# lightbulb-clock.net
KiCad netlist of a schematic drawn in EAGLE
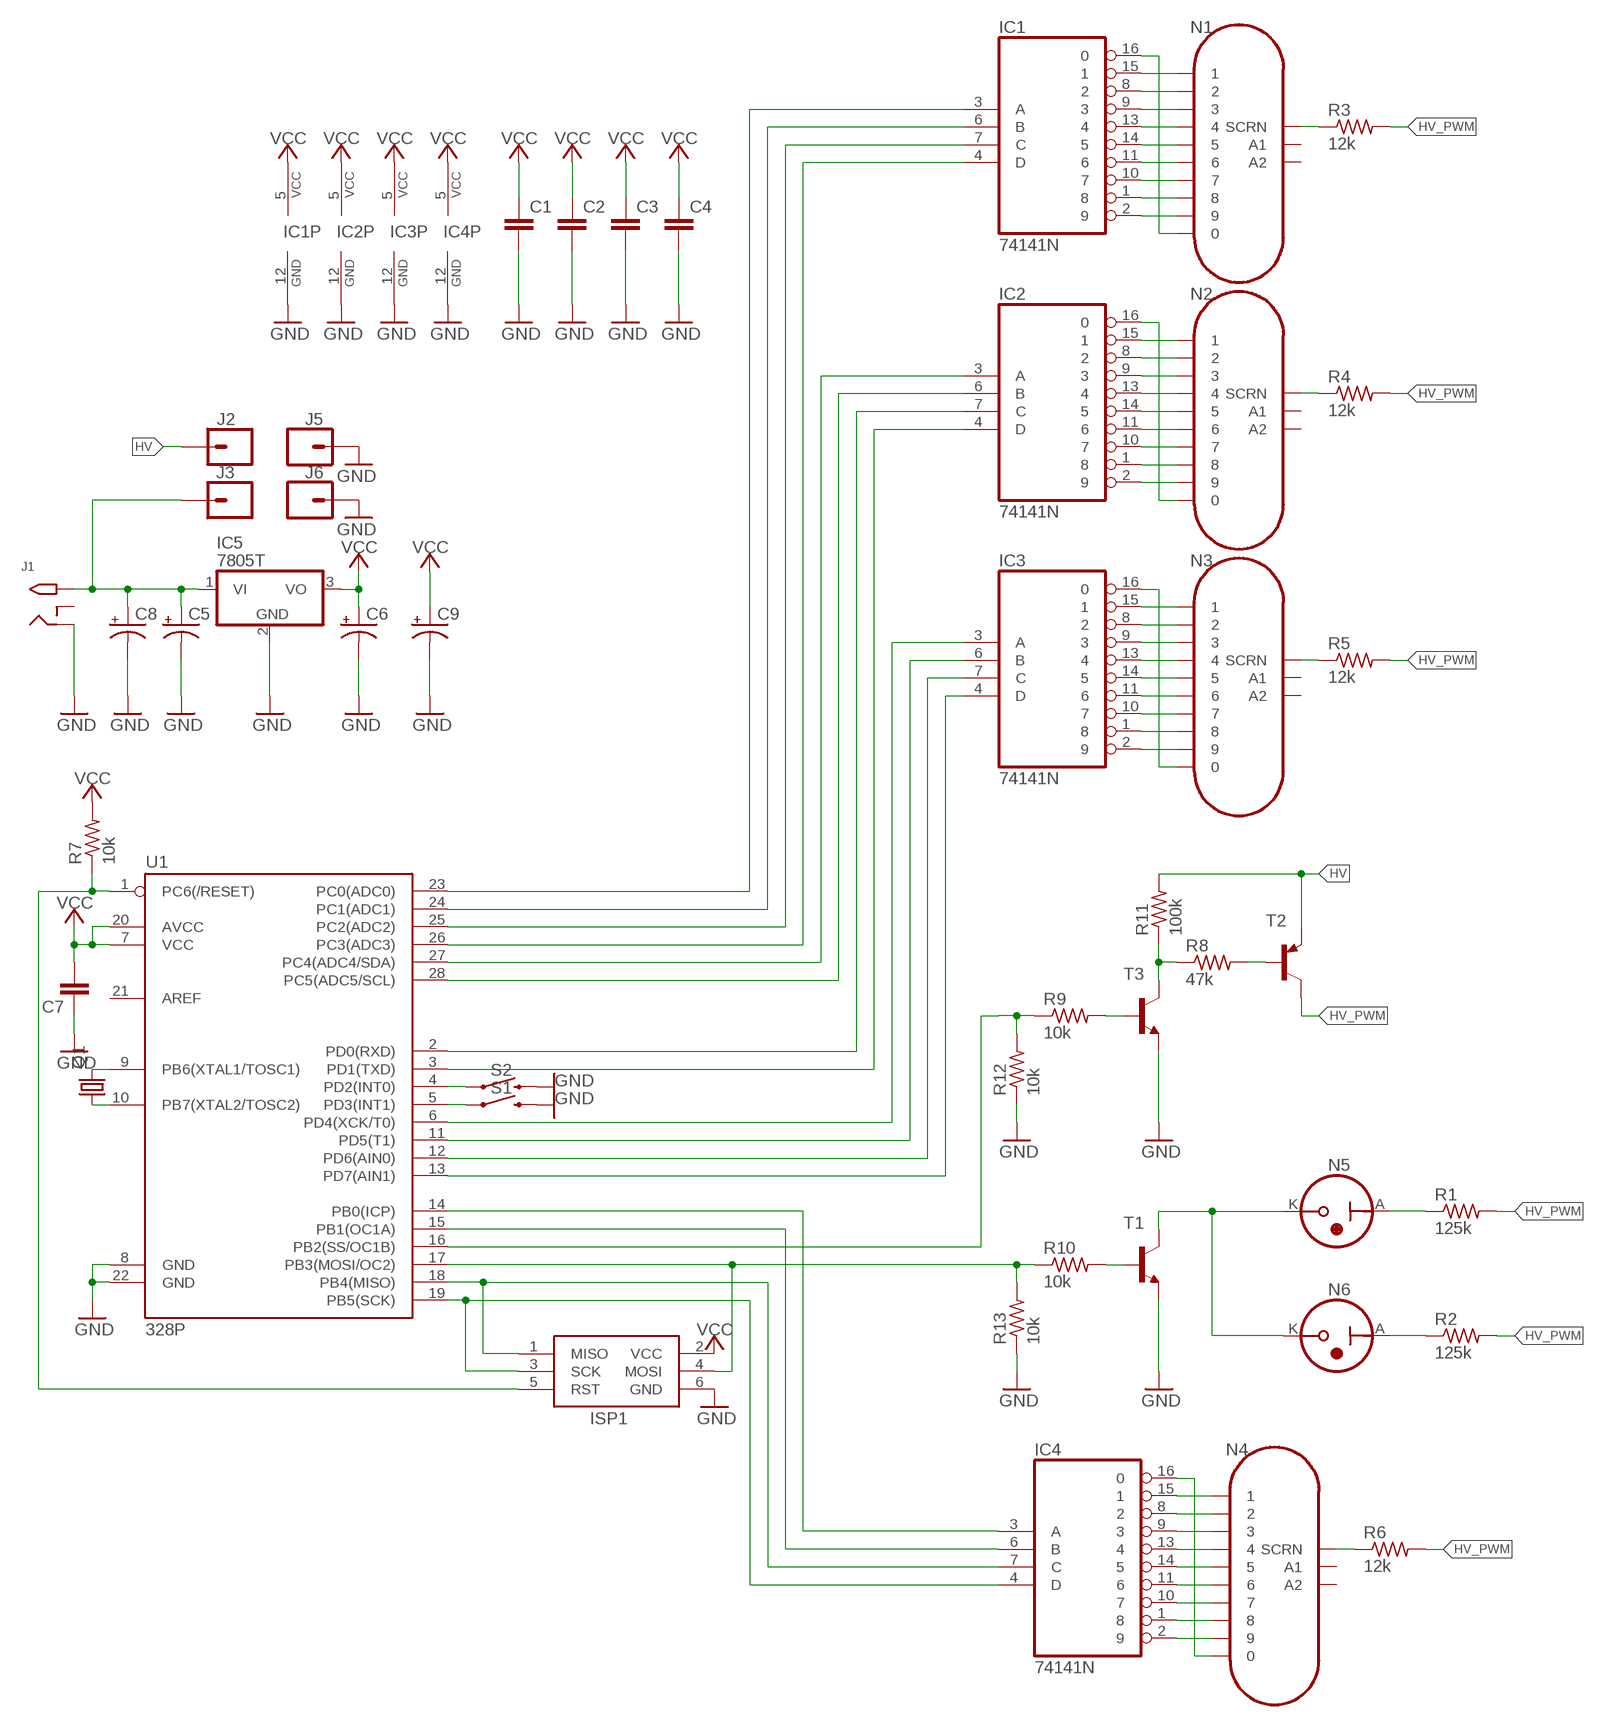
[diagram p0: schematic, sheet 1]

(export (version "E")
  (design (tool "Eeschema 10.0.6"))
  (components
    (comp (ref "C1")
      (value "C-EU025-024X044")
      (footprint "eagle-import:C025-024X044")
      (libsource (lib "eagle-import") (part "C-EU025-024X044"))
    )
    (comp (ref "C2")
      (value "C-EU025-024X044")
      (footprint "eagle-import:C025-024X044")
      (libsource (lib "eagle-import") (part "C-EU025-024X044"))
    )
    (comp (ref "C3")
      (value "C-EU025-024X044")
      (footprint "eagle-import:C025-024X044")
      (libsource (lib "eagle-import") (part "C-EU025-024X044"))
    )
    (comp (ref "C4")
      (value "C-EU025-024X044")
      (footprint "eagle-import:C025-024X044")
      (libsource (lib "eagle-import") (part "C-EU025-024X044"))
    )
    (comp (ref "C5")
      (value "CPOL-USE3.5-8")
      (footprint "eagle-import:E3,5-8")
      (libsource (lib "eagle-import") (part "CPOL-USE3.5-8"))
    )
    (comp (ref "C6")
      (value "CPOL-USE3.5-8")
      (footprint "eagle-import:E3,5-8")
      (libsource (lib "eagle-import") (part "CPOL-USE3.5-8"))
    )
    (comp (ref "C7")
      (value "C-EU025-024X044")
      (footprint "eagle-import:C025-024X044")
      (libsource (lib "eagle-import") (part "C-EU025-024X044"))
    )
    (comp (ref "C8")
      (value "CPOL-USE3.5-8")
      (footprint "eagle-import:E3,5-8")
      (libsource (lib "eagle-import") (part "CPOL-USE3.5-8"))
    )
    (comp (ref "C9")
      (value "CPOL-USE3.5-8")
      (footprint "eagle-import:E3,5-8")
      (libsource (lib "eagle-import") (part "CPOL-USE3.5-8"))
    )
    (comp (ref "IC1")
      (value "74141N")
      (footprint "eagle-import:DIL16")
      (libsource (lib "eagle-import") (part "74141N"))
    )
    (comp (ref "IC2")
      (value "74141N")
      (footprint "eagle-import:DIL16")
      (libsource (lib "eagle-import") (part "74141N"))
    )
    (comp (ref "IC3")
      (value "74141N")
      (footprint "eagle-import:DIL16")
      (libsource (lib "eagle-import") (part "74141N"))
    )
    (comp (ref "IC4")
      (value "74141N")
      (footprint "eagle-import:DIL16")
      (libsource (lib "eagle-import") (part "74141N"))
    )
    (comp (ref "IC5")
      (value "7805T")
      (footprint "eagle-import:TO220H")
      (libsource (lib "eagle-import") (part "78T05"))
    )
    (comp (ref "ISP1")
      (value "AVRISP-6")
      (footprint "eagle-import:AVRISP")
      (libsource (lib "eagle-import") (part "AVRISP-6"))
    )
    (comp (ref "J1")
      (value "2.1MMJACKTHM")
      (footprint "eagle-import:PJ-102A")
      (libsource (lib "eagle-import") (part "2.1MMJACKTHM"))
    )
    (comp (ref "J2")
      (value "CONN_01")
      (footprint "eagle-import:1X01")
      (libsource (lib "eagle-import") (part "CONN_01"))
    )
    (comp (ref "J3")
      (value "CONN_01")
      (footprint "eagle-import:1X01")
      (libsource (lib "eagle-import") (part "CONN_01"))
    )
    (comp (ref "J5")
      (value "CONN_01")
      (footprint "eagle-import:1X01")
      (libsource (lib "eagle-import") (part "CONN_01"))
    )
    (comp (ref "J6")
      (value "CONN_01")
      (footprint "eagle-import:1X01")
      (libsource (lib "eagle-import") (part "CONN_01"))
    )
    (comp (ref "N1")
      (value "IN-4")
      (footprint "eagle-import:IN-4")
      (libsource (lib "eagle-import") (part "IN-4"))
    )
    (comp (ref "N2")
      (value "IN-4")
      (footprint "eagle-import:IN-4")
      (libsource (lib "eagle-import") (part "IN-4"))
    )
    (comp (ref "N3")
      (value "IN-4")
      (footprint "eagle-import:IN-4")
      (libsource (lib "eagle-import") (part "IN-4"))
    )
    (comp (ref "N4")
      (value "IN-4")
      (footprint "eagle-import:IN-4")
      (libsource (lib "eagle-import") (part "IN-4"))
    )
    (comp (ref "N5")
      (value "INS-1")
      (footprint "eagle-import:INS-1")
      (libsource (lib "eagle-import") (part "INS-1"))
    )
    (comp (ref "N6")
      (value "INS-1")
      (footprint "eagle-import:INS-1")
      (libsource (lib "eagle-import") (part "INS-1"))
    )
    (comp (ref "Q1")
      (value "CRYSTALTC26H")
      (footprint "eagle-import:TC26H")
      (libsource (lib "eagle-import") (part "CRYSTALTC26H"))
    )
    (comp (ref "R1")
      (value "125k")
      (footprint "eagle-import:0204_5")
      (libsource (lib "eagle-import") (part "R-US_0204/5"))
    )
    (comp (ref "R2")
      (value "125k")
      (footprint "eagle-import:0204_5")
      (libsource (lib "eagle-import") (part "R-US_0204/5"))
    )
    (comp (ref "R3")
      (value "12k")
      (footprint "eagle-import:0204_5")
      (libsource (lib "eagle-import") (part "R-US_0204/5"))
    )
    (comp (ref "R4")
      (value "12k")
      (footprint "eagle-import:0204_5")
      (libsource (lib "eagle-import") (part "R-US_0204/5"))
    )
    (comp (ref "R5")
      (value "12k")
      (footprint "eagle-import:0204_5")
      (libsource (lib "eagle-import") (part "R-US_0204/5"))
    )
    (comp (ref "R6")
      (value "12k")
      (footprint "eagle-import:0204_5")
      (libsource (lib "eagle-import") (part "R-US_0204/5"))
    )
    (comp (ref "R7")
      (value "10k")
      (footprint "eagle-import:0204_5")
      (libsource (lib "eagle-import") (part "R-US_0204/5"))
    )
    (comp (ref "R8")
      (value "47k")
      (footprint "eagle-import:0204_5")
      (libsource (lib "eagle-import") (part "R-US_0204/5"))
    )
    (comp (ref "R9")
      (value "10k")
      (footprint "eagle-import:0204_5")
      (libsource (lib "eagle-import") (part "R-US_0204/5"))
    )
    (comp (ref "R10")
      (value "10k")
      (footprint "eagle-import:0204_5")
      (libsource (lib "eagle-import") (part "R-US_0204/5"))
    )
    (comp (ref "R11")
      (value "100k")
      (footprint "eagle-import:0204_5")
      (libsource (lib "eagle-import") (part "R-US_0204/5"))
    )
    (comp (ref "R12")
      (value "10k")
      (footprint "eagle-import:0204_5")
      (libsource (lib "eagle-import") (part "R-US_0204/5"))
    )
    (comp (ref "R13")
      (value "10k")
      (footprint "eagle-import:0204_5")
      (libsource (lib "eagle-import") (part "R-US_0204/5"))
    )
    (comp (ref "S1")
      (value "MOMENTARY-SWITCH-SPST-PTH-6.0MM")
      (footprint "eagle-import:TACTILE_SWITCH_PTH_6.0MM")
      (libsource (lib "eagle-import") (part "MOMENTARY-SWITCH-SPST-PTH-6.0MM"))
    )
    (comp (ref "S2")
      (value "MOMENTARY-SWITCH-SPST-PTH-6.0MM")
      (footprint "eagle-import:TACTILE_SWITCH_PTH_6.0MM")
      (libsource (lib "eagle-import") (part "MOMENTARY-SWITCH-SPST-PTH-6.0MM"))
    )
    (comp (ref "T1")
      (value "MPSA42-NPN-TO92-EBC")
      (footprint "eagle-import:TO92-EBC")
      (libsource (lib "eagle-import") (part "-NPN-TO92-EBCMPSA42"))
    )
    (comp (ref "T2")
      (value "MPSA92-PNP-TO92-EBC")
      (footprint "eagle-import:TO92-EBC")
      (libsource (lib "eagle-import") (part "-PNP-TO92-EBCMPSA92"))
    )
    (comp (ref "T3")
      (value "MPSA42-NPN-TO92-EBC")
      (footprint "eagle-import:TO92-EBC")
      (libsource (lib "eagle-import") (part "-NPN-TO92-EBCMPSA42"))
    )
    (comp (ref "U1")
      (value "328P")
      (footprint "eagle-import:DIP28")
      (libsource (lib "eagle-import") (part "ATMEGA328P_PDIP"))
    )
  )
  (nets
    (net (code "1") (name "GND") (class "Default")
      (node (ref "C1") (pin "2") (pinfunction "2_2") (pintype "passive"))
      (node (ref "C2") (pin "2") (pinfunction "2_2") (pintype "passive"))
      (node (ref "C3") (pin "2") (pinfunction "2_2") (pintype "passive"))
      (node (ref "C4") (pin "2") (pinfunction "2_2") (pintype "passive"))
      (node (ref "C5") (pin "-") (pinfunction "-_-") (pintype "passive"))
      (node (ref "C6") (pin "-") (pinfunction "-_-") (pintype "passive"))
      (node (ref "C7") (pin "1") (pinfunction "1_1") (pintype "passive"))
      (node (ref "C8") (pin "-") (pinfunction "-_-") (pintype "passive"))
      (node (ref "C9") (pin "-") (pinfunction "-_-") (pintype "passive"))
      (node (ref "IC1") (pin "12") (pinfunction "GND_12") (pintype "power_in"))
      (node (ref "IC2") (pin "12") (pinfunction "GND_12") (pintype "power_in"))
      (node (ref "IC3") (pin "12") (pinfunction "GND_12") (pintype "power_in"))
      (node (ref "IC4") (pin "12") (pinfunction "GND_12") (pintype "power_in"))
      (node (ref "IC5") (pin "2") (pinfunction "GND_2") (pintype "passive"))
      (node (ref "ISP1") (pin "6") (pinfunction "GND_6") (pintype "power_in"))
      (node (ref "J1") (pin "RING") (pinfunction "RING_RING") (pintype "bidirectional"))
      (node (ref "J5") (pin "1") (pinfunction "1_1") (pintype "passive"))
      (node (ref "J6") (pin "1") (pinfunction "1_1") (pintype "passive"))
      (node (ref "R12") (pin "1") (pinfunction "1_1") (pintype "passive"))
      (node (ref "R13") (pin "1") (pinfunction "1_1") (pintype "passive"))
      (node (ref "S1") (pin "3") (pinfunction "2_3") (pintype "passive"))
      (node (ref "S2") (pin "3") (pinfunction "2_3") (pintype "passive"))
      (node (ref "T1") (pin "E") (pinfunction "E_E") (pintype "passive"))
      (node (ref "T3") (pin "E") (pinfunction "E_E") (pintype "passive"))
      (node (ref "U1") (pin "22") (pinfunction "GND_22") (pintype "bidirectional"))
      (node (ref "U1") (pin "8") (pinfunction "GND_8") (pintype "bidirectional"))
    )
    (net (code "2") (name "HV") (class "Default")
      (node (ref "J2") (pin "1") (pinfunction "1_1") (pintype "passive"))
      (node (ref "R11") (pin "2") (pinfunction "2_2") (pintype "passive"))
      (node (ref "T2") (pin "E") (pinfunction "E_E") (pintype "passive"))
    )
    (net (code "3") (name "HV_PWM") (class "Default")
      (node (ref "R1") (pin "2") (pinfunction "2_2") (pintype "passive"))
      (node (ref "R2") (pin "2") (pinfunction "2_2") (pintype "passive"))
      (node (ref "R3") (pin "2") (pinfunction "2_2") (pintype "passive"))
      (node (ref "R4") (pin "2") (pinfunction "2_2") (pintype "passive"))
      (node (ref "R5") (pin "2") (pinfunction "2_2") (pintype "passive"))
      (node (ref "R6") (pin "2") (pinfunction "2_2") (pintype "passive"))
      (node (ref "T2") (pin "C") (pinfunction "C_C") (pintype "passive"))
    )
    (net (code "4") (name "Net-(IC1A-0)") (class "Default")
      (node (ref "IC1") (pin "16") (pinfunction "0_16") (pintype "open_collector"))
      (node (ref "N1") (pin "0") (pinfunction "0_0") (pintype "bidirectional"))
    )
    (net (code "5") (name "Net-(IC1A-1)") (class "Default")
      (node (ref "IC1") (pin "15") (pinfunction "1_15") (pintype "open_collector"))
      (node (ref "N1") (pin "1") (pinfunction "1_1") (pintype "bidirectional"))
    )
    (net (code "6") (name "Net-(IC1A-2)") (class "Default")
      (node (ref "IC1") (pin "8") (pinfunction "2_8") (pintype "open_collector"))
      (node (ref "N1") (pin "2") (pinfunction "2_2") (pintype "bidirectional"))
    )
    (net (code "7") (name "Net-(IC1A-3)") (class "Default")
      (node (ref "IC1") (pin "9") (pinfunction "3_9") (pintype "open_collector"))
      (node (ref "N1") (pin "3") (pinfunction "3_3") (pintype "bidirectional"))
    )
    (net (code "8") (name "Net-(IC1A-4)") (class "Default")
      (node (ref "IC1") (pin "13") (pinfunction "4_13") (pintype "open_collector"))
      (node (ref "N1") (pin "4") (pinfunction "4_4") (pintype "bidirectional"))
    )
    (net (code "9") (name "Net-(IC1A-5)") (class "Default")
      (node (ref "IC1") (pin "14") (pinfunction "5_14") (pintype "open_collector"))
      (node (ref "N1") (pin "5") (pinfunction "5_5") (pintype "bidirectional"))
    )
    (net (code "10") (name "Net-(IC1A-6)") (class "Default")
      (node (ref "IC1") (pin "11") (pinfunction "6_11") (pintype "open_collector"))
      (node (ref "N1") (pin "6") (pinfunction "6_6") (pintype "bidirectional"))
    )
    (net (code "11") (name "Net-(IC1A-7)") (class "Default")
      (node (ref "IC1") (pin "10") (pinfunction "7_10") (pintype "open_collector"))
      (node (ref "N1") (pin "7") (pinfunction "7_7") (pintype "bidirectional"))
    )
    (net (code "12") (name "Net-(IC1A-8)") (class "Default")
      (node (ref "IC1") (pin "1") (pinfunction "8_1") (pintype "open_collector"))
      (node (ref "N1") (pin "8") (pinfunction "8_8") (pintype "bidirectional"))
    )
    (net (code "13") (name "Net-(IC1A-9)") (class "Default")
      (node (ref "IC1") (pin "2") (pinfunction "9_2") (pintype "open_collector"))
      (node (ref "N1") (pin "9") (pinfunction "9_9") (pintype "bidirectional"))
    )
    (net (code "14") (name "Net-(IC1A-A)") (class "Default")
      (node (ref "IC1") (pin "3") (pinfunction "A_3") (pintype "input"))
      (node (ref "U1") (pin "23") (pinfunction "PC0(ADC0)_23") (pintype "bidirectional"))
    )
    (net (code "15") (name "Net-(IC1A-B)") (class "Default")
      (node (ref "IC1") (pin "6") (pinfunction "B_6") (pintype "input"))
      (node (ref "U1") (pin "24") (pinfunction "PC1(ADC1)_24") (pintype "bidirectional"))
    )
    (net (code "16") (name "Net-(IC1A-C)") (class "Default")
      (node (ref "IC1") (pin "7") (pinfunction "C_7") (pintype "input"))
      (node (ref "U1") (pin "25") (pinfunction "PC2(ADC2)_25") (pintype "bidirectional"))
    )
    (net (code "17") (name "Net-(IC1A-D)") (class "Default")
      (node (ref "IC1") (pin "4") (pinfunction "D_4") (pintype "input"))
      (node (ref "U1") (pin "26") (pinfunction "PC3(ADC3)_26") (pintype "bidirectional"))
    )
    (net (code "18") (name "Net-(IC2A-0)") (class "Default")
      (node (ref "IC2") (pin "16") (pinfunction "0_16") (pintype "open_collector"))
      (node (ref "N2") (pin "0") (pinfunction "0_0") (pintype "bidirectional"))
    )
    (net (code "19") (name "Net-(IC2A-1)") (class "Default")
      (node (ref "IC2") (pin "15") (pinfunction "1_15") (pintype "open_collector"))
      (node (ref "N2") (pin "1") (pinfunction "1_1") (pintype "bidirectional"))
    )
    (net (code "20") (name "Net-(IC2A-2)") (class "Default")
      (node (ref "IC2") (pin "8") (pinfunction "2_8") (pintype "open_collector"))
      (node (ref "N2") (pin "2") (pinfunction "2_2") (pintype "bidirectional"))
    )
    (net (code "21") (name "Net-(IC2A-3)") (class "Default")
      (node (ref "IC2") (pin "9") (pinfunction "3_9") (pintype "open_collector"))
      (node (ref "N2") (pin "3") (pinfunction "3_3") (pintype "bidirectional"))
    )
    (net (code "22") (name "Net-(IC2A-4)") (class "Default")
      (node (ref "IC2") (pin "13") (pinfunction "4_13") (pintype "open_collector"))
      (node (ref "N2") (pin "4") (pinfunction "4_4") (pintype "bidirectional"))
    )
    (net (code "23") (name "Net-(IC2A-5)") (class "Default")
      (node (ref "IC2") (pin "14") (pinfunction "5_14") (pintype "open_collector"))
      (node (ref "N2") (pin "5") (pinfunction "5_5") (pintype "bidirectional"))
    )
    (net (code "24") (name "Net-(IC2A-6)") (class "Default")
      (node (ref "IC2") (pin "11") (pinfunction "6_11") (pintype "open_collector"))
      (node (ref "N2") (pin "6") (pinfunction "6_6") (pintype "bidirectional"))
    )
    (net (code "25") (name "Net-(IC2A-7)") (class "Default")
      (node (ref "IC2") (pin "10") (pinfunction "7_10") (pintype "open_collector"))
      (node (ref "N2") (pin "7") (pinfunction "7_7") (pintype "bidirectional"))
    )
    (net (code "26") (name "Net-(IC2A-8)") (class "Default")
      (node (ref "IC2") (pin "1") (pinfunction "8_1") (pintype "open_collector"))
      (node (ref "N2") (pin "8") (pinfunction "8_8") (pintype "bidirectional"))
    )
    (net (code "27") (name "Net-(IC2A-9)") (class "Default")
      (node (ref "IC2") (pin "2") (pinfunction "9_2") (pintype "open_collector"))
      (node (ref "N2") (pin "9") (pinfunction "9_9") (pintype "bidirectional"))
    )
    (net (code "28") (name "Net-(IC2A-A)") (class "Default")
      (node (ref "IC2") (pin "3") (pinfunction "A_3") (pintype "input"))
      (node (ref "U1") (pin "27") (pinfunction "PC4(ADC4/SDA)_27") (pintype "bidirectional"))
    )
    (net (code "29") (name "Net-(IC2A-B)") (class "Default")
      (node (ref "IC2") (pin "6") (pinfunction "B_6") (pintype "input"))
      (node (ref "U1") (pin "28") (pinfunction "PC5(ADC5/SCL)_28") (pintype "bidirectional"))
    )
    (net (code "30") (name "Net-(IC2A-C)") (class "Default")
      (node (ref "IC2") (pin "7") (pinfunction "C_7") (pintype "input"))
      (node (ref "U1") (pin "2") (pinfunction "PD0(RXD)_2") (pintype "bidirectional"))
    )
    (net (code "31") (name "Net-(IC2A-D)") (class "Default")
      (node (ref "IC2") (pin "4") (pinfunction "D_4") (pintype "input"))
      (node (ref "U1") (pin "3") (pinfunction "PD1(TXD)_3") (pintype "bidirectional"))
    )
    (net (code "32") (name "Net-(IC3A-0)") (class "Default")
      (node (ref "IC3") (pin "16") (pinfunction "0_16") (pintype "open_collector"))
      (node (ref "N3") (pin "0") (pinfunction "0_0") (pintype "bidirectional"))
    )
    (net (code "33") (name "Net-(IC3A-1)") (class "Default")
      (node (ref "IC3") (pin "15") (pinfunction "1_15") (pintype "open_collector"))
      (node (ref "N3") (pin "1") (pinfunction "1_1") (pintype "bidirectional"))
    )
    (net (code "34") (name "Net-(IC3A-2)") (class "Default")
      (node (ref "IC3") (pin "8") (pinfunction "2_8") (pintype "open_collector"))
      (node (ref "N3") (pin "2") (pinfunction "2_2") (pintype "bidirectional"))
    )
    (net (code "35") (name "Net-(IC3A-3)") (class "Default")
      (node (ref "IC3") (pin "9") (pinfunction "3_9") (pintype "open_collector"))
      (node (ref "N3") (pin "3") (pinfunction "3_3") (pintype "bidirectional"))
    )
    (net (code "36") (name "Net-(IC3A-4)") (class "Default")
      (node (ref "IC3") (pin "13") (pinfunction "4_13") (pintype "open_collector"))
      (node (ref "N3") (pin "4") (pinfunction "4_4") (pintype "bidirectional"))
    )
    (net (code "37") (name "Net-(IC3A-5)") (class "Default")
      (node (ref "IC3") (pin "14") (pinfunction "5_14") (pintype "open_collector"))
      (node (ref "N3") (pin "5") (pinfunction "5_5") (pintype "bidirectional"))
    )
    (net (code "38") (name "Net-(IC3A-6)") (class "Default")
      (node (ref "IC3") (pin "11") (pinfunction "6_11") (pintype "open_collector"))
      (node (ref "N3") (pin "6") (pinfunction "6_6") (pintype "bidirectional"))
    )
    (net (code "39") (name "Net-(IC3A-7)") (class "Default")
      (node (ref "IC3") (pin "10") (pinfunction "7_10") (pintype "open_collector"))
      (node (ref "N3") (pin "7") (pinfunction "7_7") (pintype "bidirectional"))
    )
    (net (code "40") (name "Net-(IC3A-8)") (class "Default")
      (node (ref "IC3") (pin "1") (pinfunction "8_1") (pintype "open_collector"))
      (node (ref "N3") (pin "8") (pinfunction "8_8") (pintype "bidirectional"))
    )
    (net (code "41") (name "Net-(IC3A-9)") (class "Default")
      (node (ref "IC3") (pin "2") (pinfunction "9_2") (pintype "open_collector"))
      (node (ref "N3") (pin "9") (pinfunction "9_9") (pintype "bidirectional"))
    )
    (net (code "42") (name "Net-(IC3A-A)") (class "Default")
      (node (ref "IC3") (pin "3") (pinfunction "A_3") (pintype "input"))
      (node (ref "U1") (pin "6") (pinfunction "PD4(XCK/T0)_6") (pintype "bidirectional"))
    )
    (net (code "43") (name "Net-(IC3A-B)") (class "Default")
      (node (ref "IC3") (pin "6") (pinfunction "B_6") (pintype "input"))
      (node (ref "U1") (pin "11") (pinfunction "PD5(T1)_11") (pintype "bidirectional"))
    )
    (net (code "44") (name "Net-(IC3A-C)") (class "Default")
      (node (ref "IC3") (pin "7") (pinfunction "C_7") (pintype "input"))
      (node (ref "U1") (pin "12") (pinfunction "PD6(AIN0)_12") (pintype "bidirectional"))
    )
    (net (code "45") (name "Net-(IC3A-D)") (class "Default")
      (node (ref "IC3") (pin "4") (pinfunction "D_4") (pintype "input"))
      (node (ref "U1") (pin "13") (pinfunction "PD7(AIN1)_13") (pintype "bidirectional"))
    )
    (net (code "46") (name "Net-(IC4A-0)") (class "Default")
      (node (ref "IC4") (pin "16") (pinfunction "0_16") (pintype "open_collector"))
      (node (ref "N4") (pin "0") (pinfunction "0_0") (pintype "bidirectional"))
    )
    (net (code "47") (name "Net-(IC4A-1)") (class "Default")
      (node (ref "IC4") (pin "15") (pinfunction "1_15") (pintype "open_collector"))
      (node (ref "N4") (pin "1") (pinfunction "1_1") (pintype "bidirectional"))
    )
    (net (code "48") (name "Net-(IC4A-2)") (class "Default")
      (node (ref "IC4") (pin "8") (pinfunction "2_8") (pintype "open_collector"))
      (node (ref "N4") (pin "2") (pinfunction "2_2") (pintype "bidirectional"))
    )
    (net (code "49") (name "Net-(IC4A-3)") (class "Default")
      (node (ref "IC4") (pin "9") (pinfunction "3_9") (pintype "open_collector"))
      (node (ref "N4") (pin "3") (pinfunction "3_3") (pintype "bidirectional"))
    )
    (net (code "50") (name "Net-(IC4A-4)") (class "Default")
      (node (ref "IC4") (pin "13") (pinfunction "4_13") (pintype "open_collector"))
      (node (ref "N4") (pin "4") (pinfunction "4_4") (pintype "bidirectional"))
    )
    (net (code "51") (name "Net-(IC4A-5)") (class "Default")
      (node (ref "IC4") (pin "14") (pinfunction "5_14") (pintype "open_collector"))
      (node (ref "N4") (pin "5") (pinfunction "5_5") (pintype "bidirectional"))
    )
    (net (code "52") (name "Net-(IC4A-6)") (class "Default")
      (node (ref "IC4") (pin "11") (pinfunction "6_11") (pintype "open_collector"))
      (node (ref "N4") (pin "6") (pinfunction "6_6") (pintype "bidirectional"))
    )
    (net (code "53") (name "Net-(IC4A-7)") (class "Default")
      (node (ref "IC4") (pin "10") (pinfunction "7_10") (pintype "open_collector"))
      (node (ref "N4") (pin "7") (pinfunction "7_7") (pintype "bidirectional"))
    )
    (net (code "54") (name "Net-(IC4A-8)") (class "Default")
      (node (ref "IC4") (pin "1") (pinfunction "8_1") (pintype "open_collector"))
      (node (ref "N4") (pin "8") (pinfunction "8_8") (pintype "bidirectional"))
    )
    (net (code "55") (name "Net-(IC4A-9)") (class "Default")
      (node (ref "IC4") (pin "2") (pinfunction "9_2") (pintype "open_collector"))
      (node (ref "N4") (pin "9") (pinfunction "9_9") (pintype "bidirectional"))
    )
    (net (code "56") (name "Net-(IC4A-A)") (class "Default")
      (node (ref "IC4") (pin "3") (pinfunction "A_3") (pintype "input"))
      (node (ref "U1") (pin "14") (pinfunction "PB0(ICP)_14") (pintype "bidirectional"))
    )
    (net (code "57") (name "Net-(IC4A-B)") (class "Default")
      (node (ref "IC4") (pin "6") (pinfunction "B_6") (pintype "input"))
      (node (ref "U1") (pin "15") (pinfunction "PB1(OC1A)_15") (pintype "bidirectional"))
    )
    (net (code "58") (name "Net-(IC4A-C)") (class "Default")
      (node (ref "IC4") (pin "7") (pinfunction "C_7") (pintype "input"))
      (node (ref "ISP1") (pin "1") (pinfunction "MISO_1") (pintype "input"))
      (node (ref "U1") (pin "18") (pinfunction "PB4(MISO)_18") (pintype "bidirectional"))
    )
    (net (code "59") (name "Net-(IC4A-D)") (class "Default")
      (node (ref "IC4") (pin "4") (pinfunction "D_4") (pintype "input"))
      (node (ref "ISP1") (pin "3") (pinfunction "SCK_3") (pintype "output"))
      (node (ref "U1") (pin "19") (pinfunction "PB5(SCK)_19") (pintype "bidirectional"))
    )
    (net (code "60") (name "Net-(IC5-VI)") (class "Default")
      (node (ref "C5") (pin "+") (pinfunction "+_+") (pintype "passive"))
      (node (ref "C8") (pin "+") (pinfunction "+_+") (pintype "passive"))
      (node (ref "IC5") (pin "1") (pinfunction "VI_1") (pintype "input"))
      (node (ref "J1") (pin "TIP") (pinfunction "TIP_TIP") (pintype "bidirectional"))
      (node (ref "J3") (pin "1") (pinfunction "1_1") (pintype "passive"))
    )
    (net (code "61") (name "Net-(ISP1-MOSI)") (class "Default")
      (node (ref "ISP1") (pin "4") (pinfunction "MOSI_4") (pintype "output"))
      (node (ref "R10") (pin "1") (pinfunction "1_1") (pintype "passive"))
      (node (ref "R13") (pin "2") (pinfunction "2_2") (pintype "passive"))
      (node (ref "U1") (pin "17") (pinfunction "PB3(MOSI/OC2)_17") (pintype "bidirectional"))
    )
    (net (code "62") (name "Net-(ISP1-RST)") (class "Default")
      (node (ref "ISP1") (pin "5") (pinfunction "RST_5") (pintype "output"))
      (node (ref "R7") (pin "1") (pinfunction "1_1") (pintype "passive"))
      (node (ref "U1") (pin "1") (pinfunction "PC6(/RESET)_1") (pintype "bidirectional"))
    )
    (net (code "63") (name "Net-(N1-SCRN)") (class "Default")
      (node (ref "N1") (pin "S") (pinfunction "SCRN_S") (pintype "bidirectional"))
      (node (ref "R3") (pin "1") (pinfunction "1_1") (pintype "passive"))
    )
    (net (code "64") (name "Net-(N2-SCRN)") (class "Default")
      (node (ref "N2") (pin "S") (pinfunction "SCRN_S") (pintype "bidirectional"))
      (node (ref "R4") (pin "1") (pinfunction "1_1") (pintype "passive"))
    )
    (net (code "65") (name "Net-(N3-SCRN)") (class "Default")
      (node (ref "N3") (pin "S") (pinfunction "SCRN_S") (pintype "bidirectional"))
      (node (ref "R5") (pin "1") (pinfunction "1_1") (pintype "passive"))
    )
    (net (code "66") (name "Net-(N4-SCRN)") (class "Default")
      (node (ref "N4") (pin "S") (pinfunction "SCRN_S") (pintype "bidirectional"))
      (node (ref "R6") (pin "1") (pinfunction "1_1") (pintype "passive"))
    )
    (net (code "67") (name "Net-(N5-PadA)") (class "Default")
      (node (ref "N5") (pin "A") (pinfunction "A_A") (pintype "bidirectional"))
      (node (ref "R1") (pin "1") (pinfunction "1_1") (pintype "passive"))
    )
    (net (code "68") (name "Net-(N5-PadK)") (class "Default")
      (node (ref "N5") (pin "K") (pinfunction "K_K") (pintype "bidirectional"))
      (node (ref "N6") (pin "K") (pinfunction "K_K") (pintype "bidirectional"))
      (node (ref "T1") (pin "C") (pinfunction "C_C") (pintype "passive"))
    )
    (net (code "69") (name "Net-(N6-PadA)") (class "Default")
      (node (ref "N6") (pin "A") (pinfunction "A_A") (pintype "bidirectional"))
      (node (ref "R2") (pin "1") (pinfunction "1_1") (pintype "passive"))
    )
    (net (code "70") (name "Net-(R8-Pad2)") (class "Default")
      (node (ref "R8") (pin "2") (pinfunction "2_2") (pintype "passive"))
      (node (ref "T2") (pin "B") (pinfunction "B_B") (pintype "passive"))
    )
    (net (code "71") (name "Net-(R9-Pad2)") (class "Default")
      (node (ref "R9") (pin "2") (pinfunction "2_2") (pintype "passive"))
      (node (ref "T3") (pin "B") (pinfunction "B_B") (pintype "passive"))
    )
    (net (code "72") (name "Net-(R10-Pad2)") (class "Default")
      (node (ref "R10") (pin "2") (pinfunction "2_2") (pintype "passive"))
      (node (ref "T1") (pin "B") (pinfunction "B_B") (pintype "passive"))
    )
    (net (code "73") (name "Net-(R11-Pad1)") (class "Default")
      (node (ref "R11") (pin "1") (pinfunction "1_1") (pintype "passive"))
      (node (ref "R8") (pin "1") (pinfunction "1_1") (pintype "passive"))
      (node (ref "T3") (pin "C") (pinfunction "C_C") (pintype "passive"))
    )
    (net (code "74") (name "Net-(U1-PB2(SS{slash}OC1B))") (class "Default")
      (node (ref "R12") (pin "2") (pinfunction "2_2") (pintype "passive"))
      (node (ref "R9") (pin "1") (pinfunction "1_1") (pintype "passive"))
      (node (ref "U1") (pin "16") (pinfunction "PB2(SS/OC1B)_16") (pintype "bidirectional"))
    )
    (net (code "75") (name "Net-(U1-PB6(XTAL1{slash}TOSC1))") (class "Default")
      (node (ref "Q1") (pin "2") (pinfunction "2_2") (pintype "passive"))
      (node (ref "U1") (pin "9") (pinfunction "PB6(XTAL1/TOSC1)_9") (pintype "bidirectional"))
    )
    (net (code "76") (name "Net-(U1-PB7(XTAL2{slash}TOSC2))") (class "Default")
      (node (ref "Q1") (pin "1") (pinfunction "1_1") (pintype "passive"))
      (node (ref "U1") (pin "10") (pinfunction "PB7(XTAL2/TOSC2)_10") (pintype "bidirectional"))
    )
    (net (code "77") (name "Net-(U1-PD2(INT0))") (class "Default")
      (node (ref "S2") (pin "1") (pinfunction "1_1") (pintype "passive"))
      (node (ref "U1") (pin "4") (pinfunction "PD2(INT0)_4") (pintype "bidirectional"))
    )
    (net (code "78") (name "Net-(U1-PD3(INT1))") (class "Default")
      (node (ref "S1") (pin "1") (pinfunction "1_1") (pintype "passive"))
      (node (ref "U1") (pin "5") (pinfunction "PD3(INT1)_5") (pintype "bidirectional"))
    )
    (net (code "79") (name "VCC") (class "Default")
      (node (ref "C1") (pin "1") (pinfunction "1_1") (pintype "passive"))
      (node (ref "C2") (pin "1") (pinfunction "1_1") (pintype "passive"))
      (node (ref "C3") (pin "1") (pinfunction "1_1") (pintype "passive"))
      (node (ref "C4") (pin "1") (pinfunction "1_1") (pintype "passive"))
      (node (ref "C6") (pin "+") (pinfunction "+_+") (pintype "passive"))
      (node (ref "C7") (pin "2") (pinfunction "2_2") (pintype "passive"))
      (node (ref "C9") (pin "+") (pinfunction "+_+") (pintype "passive"))
      (node (ref "IC1") (pin "5") (pinfunction "VCC_5") (pintype "power_in"))
      (node (ref "IC2") (pin "5") (pinfunction "VCC_5") (pintype "power_in"))
      (node (ref "IC3") (pin "5") (pinfunction "VCC_5") (pintype "power_in"))
      (node (ref "IC4") (pin "5") (pinfunction "VCC_5") (pintype "power_in"))
      (node (ref "IC5") (pin "3") (pinfunction "VO_3") (pintype "passive"))
      (node (ref "ISP1") (pin "2") (pinfunction "VCC_2") (pintype "power_in"))
      (node (ref "R7") (pin "2") (pinfunction "2_2") (pintype "passive"))
      (node (ref "U1") (pin "20") (pinfunction "AVCC_20") (pintype "bidirectional"))
      (node (ref "U1") (pin "7") (pinfunction "VCC_7") (pintype "bidirectional"))
    )
    (net (code "80") (name "unconnected-(J1-PadRING_SW)") (class "Default")
      (node (ref "J1") (pin "RING_SW") (pinfunction "RING_SW_RING_SW") (pintype "bidirectional"))
    )
    (net (code "81") (name "unconnected-(N1-PadA1)") (class "Default")
      (node (ref "N1") (pin "A1") (pinfunction "A1_A1") (pintype "bidirectional"))
    )
    (net (code "82") (name "unconnected-(N1-PadA2)") (class "Default")
      (node (ref "N1") (pin "A2") (pinfunction "A2_A2") (pintype "bidirectional"))
    )
    (net (code "83") (name "unconnected-(N2-PadA1)") (class "Default")
      (node (ref "N2") (pin "A1") (pinfunction "A1_A1") (pintype "bidirectional"))
    )
    (net (code "84") (name "unconnected-(N2-PadA2)") (class "Default")
      (node (ref "N2") (pin "A2") (pinfunction "A2_A2") (pintype "bidirectional"))
    )
    (net (code "85") (name "unconnected-(N3-PadA1)") (class "Default")
      (node (ref "N3") (pin "A1") (pinfunction "A1_A1") (pintype "bidirectional"))
    )
    (net (code "86") (name "unconnected-(N3-PadA2)") (class "Default")
      (node (ref "N3") (pin "A2") (pinfunction "A2_A2") (pintype "bidirectional"))
    )
    (net (code "87") (name "unconnected-(N4-PadA1)") (class "Default")
      (node (ref "N4") (pin "A1") (pinfunction "A1_A1") (pintype "bidirectional"))
    )
    (net (code "88") (name "unconnected-(N4-PadA2)") (class "Default")
      (node (ref "N4") (pin "A2") (pinfunction "A2_A2") (pintype "bidirectional"))
    )
    (net (code "89") (name "unconnected-(U1-AREF-Pad21)") (class "Default")
      (node (ref "U1") (pin "21") (pinfunction "AREF_21") (pintype "bidirectional"))
    )
  )
)
